# Thermal_Sense.net
KiCad netlist of a schematic drawn in Altium Designer
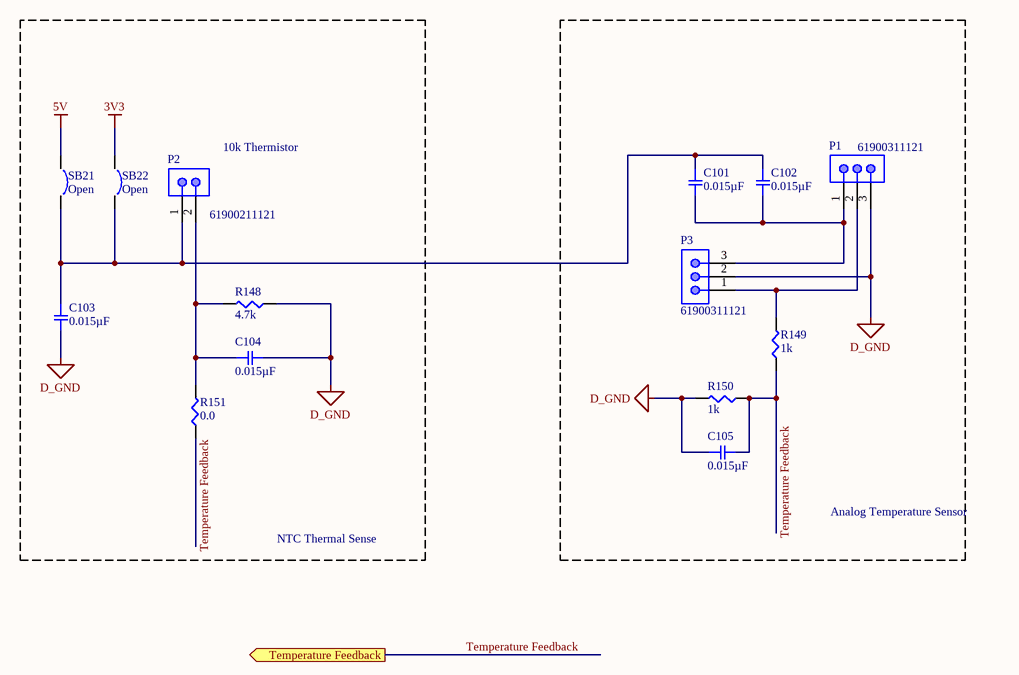
[diagram p0: Thermal_Sense.SchDoc]

(export (version "E")
  (design (tool "Eeschema 10.0.6"))
  (components
    (comp (ref "C101")
      (value "0.015µF")
      (footprint "SMD-0805C")
      (description "CAP CER 0.015UF 250V X7T 0805")
      (fields
        (field (name "DIGI-KEY PART NUMBER") "490-13987-1-ND")
        (field (name "PART NUMBER") "GC321AD72E153KX01D")
      )
      (libsource (lib "capacitor_murata_0805") (part "GC321AD72E153KX01D"))
    )
    (comp (ref "C102")
      (value "0.015µF")
      (footprint "SMD-0805C")
      (description "CAP CER 0.015UF 250V X7T 0805")
      (fields
        (field (name "DIGI-KEY PART NUMBER") "490-13987-1-ND")
        (field (name "PART NUMBER") "GC321AD72E153KX01D")
      )
      (libsource (lib "capacitor_murata_0805") (part "GC321AD72E153KX01D"))
    )
    (comp (ref "C103")
      (value "0.015µF")
      (footprint "SMD-0805C")
      (description "CAP CER 0.015UF 250V X7T 0805")
      (fields
        (field (name "DIGI-KEY PART NUMBER") "490-13987-1-ND")
        (field (name "PART NUMBER") "GC321AD72E153KX01D")
      )
      (libsource (lib "capacitor_murata_0805") (part "GC321AD72E153KX01D"))
    )
    (comp (ref "C104")
      (value "0.015µF")
      (footprint "SMD-0805C")
      (description "CAP CER 0.015UF 250V X7T 0805")
      (fields
        (field (name "DIGI-KEY PART NUMBER") "490-13987-1-ND")
        (field (name "PART NUMBER") "GC321AD72E153KX01D")
      )
      (libsource (lib "capacitor_murata_0805") (part "GC321AD72E153KX01D"))
    )
    (comp (ref "C105")
      (value "0.015µF")
      (footprint "SMD-0805C")
      (description "CAP CER 0.015UF 250V X7T 0805")
      (fields
        (field (name "DIGI-KEY PART NUMBER") "490-13987-1-ND")
        (field (name "PART NUMBER") "GC321AD72E153KX01D")
      )
      (libsource (lib "capacitor_murata_0805") (part "GC321AD72E153KX01D"))
    )
    (comp (ref "P1")
      (value "61900311121")
      (footprint "61900311121")
      (description "WR-WTB THT Male Vertical Locking Header, pitch 2.54mm, 3p")
      (fields (field (name "PUBLISHER") "Wurth Elektronik"))
      (libsource (lib "o124671v243 Altium_WR-WTB (rev20a)") (part "61900311121"))
    )
    (comp (ref "P2")
      (value "61900211121")
      (footprint "61900211121")
      (description "WR-WTB THT Male Vertical Locking Header, pitch 2.54mm, 2p")
      (fields (field (name "PUBLISHER") "Wurth Elektronik"))
      (libsource (lib "o124671v243 Altium_WR-WTB (rev20a)") (part "61900211121"))
    )
    (comp (ref "P3")
      (value "61900311121")
      (footprint "61900311121")
      (description "WR-WTB THT Male Vertical Locking Header, pitch 2.54mm, 3p")
      (fields (field (name "PUBLISHER") "Wurth Elektronik"))
      (libsource (lib "o124671v243 Altium_WR-WTB (rev20a)") (part "61900311121"))
    )
    (comp (ref "R148")
      (value "4.7k")
      (footprint "SMD-0603-RES")
      (description "RES SMD 4.7K OHM 1% 1/10W 0603")
      (fields
        (field (name "PART NUMBER") "ERJ-3EKF4701V")
        (field (name "DIGI-KEY PART NUMBER") "P4.70KHCT-ND")
      )
      (libsource (lib "Panasonic_ERJ_0603") (part "ERJ-3EKF4701V"))
    )
    (comp (ref "R149")
      (value "1k")
      (footprint "SMD-0603-RES")
      (description "RES SMD 1K OHM 1% 1/10W 0603")
      (fields
        (field (name "PART NUMBER") "ERJ-3EKF1001V")
        (field (name "DIGI-KEY PART NUMBER") "P1.00KHCT-ND")
      )
      (libsource (lib "Panasonic_ERJ_0603") (part "ERJ-3EKF1001V"))
    )
    (comp (ref "R150")
      (value "1k")
      (footprint "SMD-0603-RES")
      (description "RES SMD 1K OHM 1% 1/10W 0603")
      (fields
        (field (name "PART NUMBER") "ERJ-3EKF1001V")
        (field (name "DIGI-KEY PART NUMBER") "P1.00KHCT-ND")
      )
      (libsource (lib "Panasonic_ERJ_0603") (part "ERJ-3EKF1001V"))
    )
    (comp (ref "R151")
      (value "0.0")
      (footprint "SMD-0603-RES")
      (description "RES SMD 0.0OHM JUMPER 1/10W 0603")
      (fields (field (name "PART NUMBER") "ERJ-3GEY0R00V") (field (name "DIGI-KEY PART NUMBER") "P0.0GCT-ND"))
      (libsource (lib "Panasonic_ERJ_0603") (part "ERJ-3GEY0R00V"))
    )
    (comp (ref "SB21")
      (value "Open")
      (footprint "Solder Bridge - HP - SQ")
      (description "Circuit Breaker")
      (fields (field (name "PUBLISHER") "Altium Limited"))
      (libsource (lib "NUCLEOG431RB-Custom-IN-A2212") (part "Solder Bridge"))
    )
    (comp (ref "SB22")
      (value "Open")
      (footprint "Solder Bridge - HP - SQ")
      (description "Circuit Breaker")
      (fields (field (name "PUBLISHER") "Altium Limited"))
      (libsource (lib "NUCLEOG431RB-Custom-IN-A2212") (part "Solder Bridge"))
    )
  )
  (nets
    (net (code "1") (name "/Temperature Feedback") (class "Default")
      (node (ref "C105") (pin "2") (pinfunction "2_2") (pintype "passive"))
      (node (ref "R149") (pin "1") (pinfunction "1_1") (pintype "passive"))
      (node (ref "R150") (pin "1") (pinfunction "1_1") (pintype "passive"))
      (node (ref "R151") (pin "1") (pinfunction "1_1") (pintype "passive"))
    )
    (net (code "2") (name "3V3") (class "Default")
      (node (ref "SB22") (pin "1") (pinfunction "1_1") (pintype "passive"))
    )
    (net (code "3") (name "5V") (class "Default")
      (node (ref "SB21") (pin "1") (pinfunction "1_1") (pintype "passive"))
    )
    (net (code "4") (name "D_GND") (class "Default")
      (node (ref "C103") (pin "2") (pinfunction "2_2") (pintype "passive"))
      (node (ref "C104") (pin "2") (pinfunction "2_2") (pintype "passive"))
      (node (ref "C105") (pin "1") (pinfunction "1_1") (pintype "passive"))
      (node (ref "P1") (pin "3") (pinfunction "3_3") (pintype "passive"))
      (node (ref "P3") (pin "2") (pinfunction "2_2") (pintype "passive"))
      (node (ref "R148") (pin "1") (pinfunction "1_1") (pintype "passive"))
      (node (ref "R150") (pin "2") (pinfunction "2_2") (pintype "passive"))
    )
    (net (code "5") (name "Net-(C101-Pad1)") (class "Default")
      (node (ref "C101") (pin "1") (pinfunction "1_1") (pintype "passive"))
      (node (ref "C102") (pin "1") (pinfunction "1_1") (pintype "passive"))
      (node (ref "C103") (pin "1") (pinfunction "1_1") (pintype "passive"))
      (node (ref "P2") (pin "1") (pinfunction "1_1") (pintype "passive"))
      (node (ref "SB21") (pin "2") (pinfunction "2_2") (pintype "passive"))
      (node (ref "SB22") (pin "2") (pinfunction "2_2") (pintype "passive"))
    )
    (net (code "6") (name "Net-(C101-Pad2)") (class "Default")
      (node (ref "C101") (pin "2") (pinfunction "2_2") (pintype "passive"))
      (node (ref "C102") (pin "2") (pinfunction "2_2") (pintype "passive"))
      (node (ref "P1") (pin "1") (pinfunction "1_1") (pintype "passive"))
      (node (ref "P3") (pin "3") (pinfunction "3_3") (pintype "passive"))
    )
    (net (code "7") (name "Net-(C104-Pad1)") (class "Default")
      (node (ref "C104") (pin "1") (pinfunction "1_1") (pintype "passive"))
      (node (ref "P2") (pin "2") (pinfunction "2_2") (pintype "passive"))
      (node (ref "R148") (pin "2") (pinfunction "2_2") (pintype "passive"))
      (node (ref "R151") (pin "2") (pinfunction "2_2") (pintype "passive"))
    )
    (net (code "8") (name "Net-(P1-Pad2)") (class "Default")
      (node (ref "P1") (pin "2") (pinfunction "2_2") (pintype "passive"))
      (node (ref "P3") (pin "1") (pinfunction "1_1") (pintype "passive"))
      (node (ref "R149") (pin "2") (pinfunction "2_2") (pintype "passive"))
    )
  )
)
